# Therm_Controller.net
KiCad netlist of a schematic drawn in EasyEDA
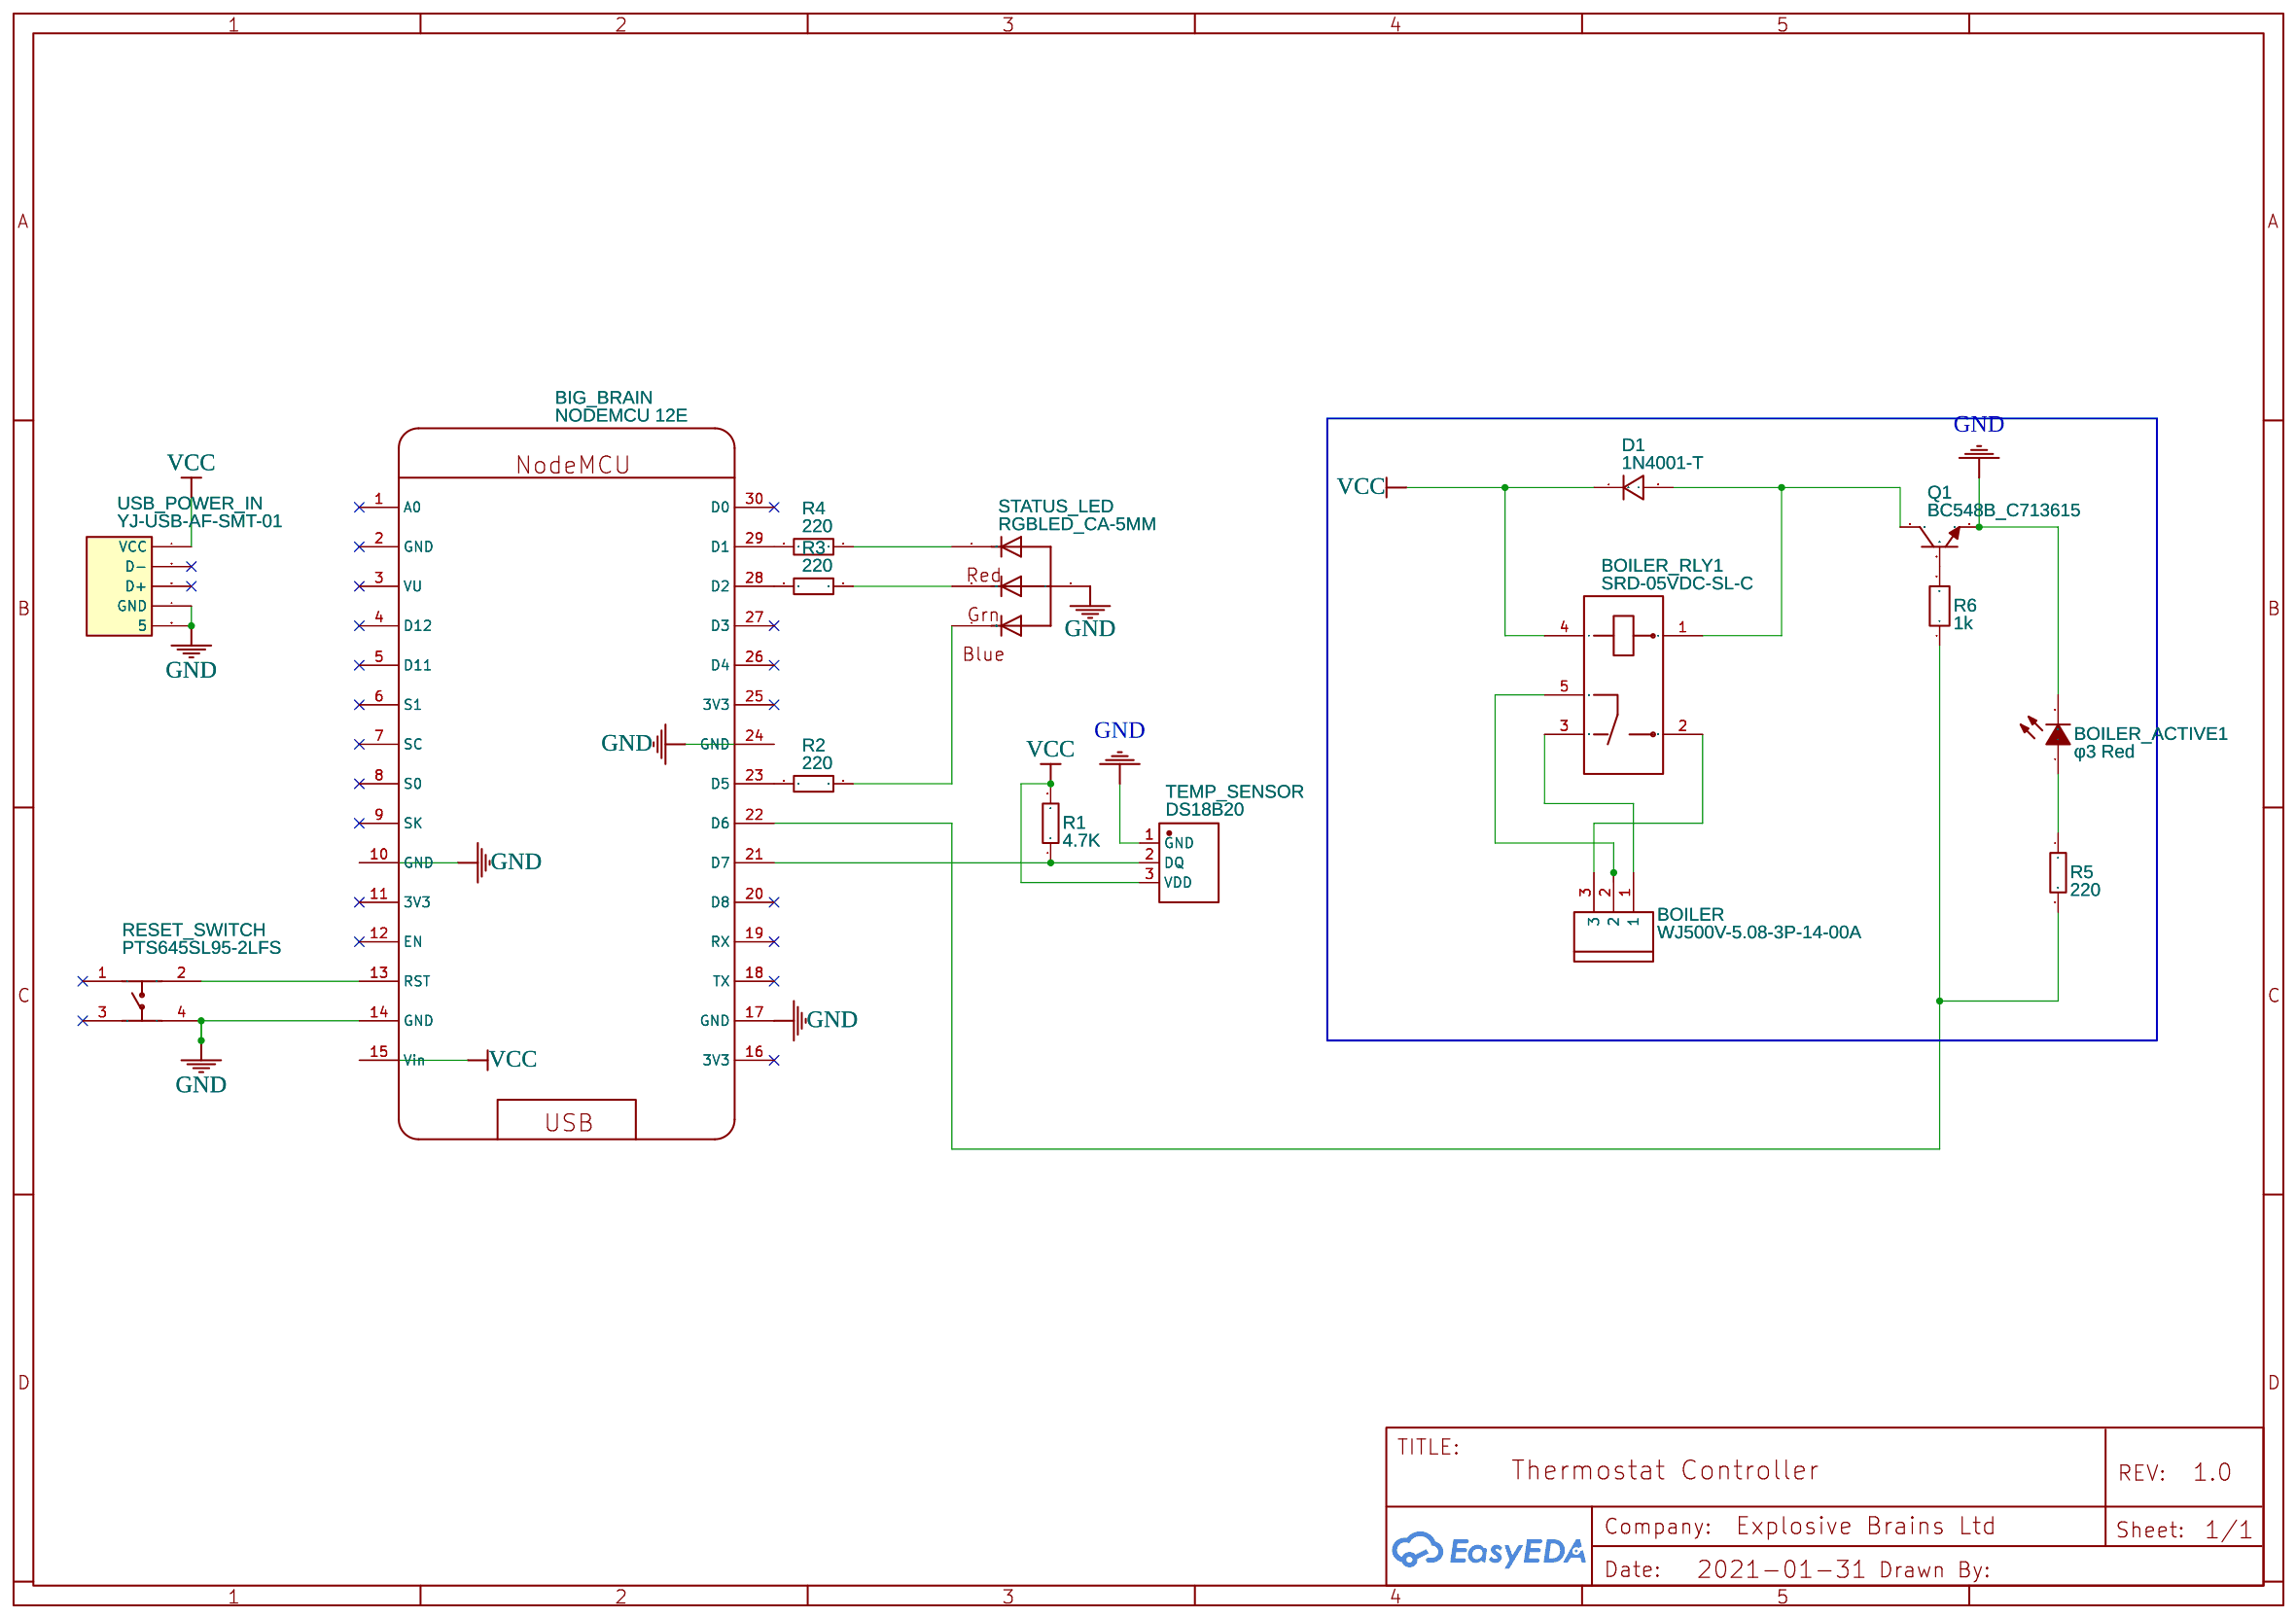
[diagram p0: schematic sheet]

(export (version "E")
  (design (tool "Eeschema 10.0.6"))
  (components
    (comp (ref "BIG_BRAIN") (value "NODEMCU 12E") (libsource (lib "") (part "NODEMCU 12E")))
    (comp (ref "BOILER")
      (value "WJ500V-5.08-3P-14-00A")
      (fields (field (name "BOM_Supplier Part") "C72334"))
      (libsource (lib "") (part "WJ500V-5.08-3P-14-00A"))
    )
    (comp (ref "BOILER_ACTIVE1")
      (value "φ3 Red")
      (fields (field (name "BOM_Supplier Part") "C39928"))
      (libsource (lib "") (part "φ3 Red"))
    )
    (comp (ref "BOILER_RLY1")
      (value "SRD-05VDC-SL-C")
      (fields (field (name "BOM_Supplier Part") "C35449"))
      (libsource (lib "") (part "SRD-05VDC-SL-C"))
    )
    (comp (ref "D1")
      (value "1N4001-T")
      (fields (field (name "BOM_Supplier Part") "C99656"))
      (libsource (lib "") (part "1N4001-T COPY"))
    )
    (comp (ref "Q1")
      (value "BC548B_C713615")
      (fields (field (name "BOM_Manufacturer Part") "BC548B") (field (name "BOM_Supplier Part") "C713615"))
      (libsource (lib "") (part "BC548B_C713615"))
    )
    (comp (ref "R1")
      (value "4.7K")
      (fields
        (field (name "BOM_Manufacturer Part") "CFR0W4J0472A50")
        (field (name "BOM_Supplier Part") "C61297")
      )
      (libsource (lib "") (part "CFR0W4J0472A50"))
    )
    (comp (ref "R2")
      (value "220")
      (fields (field (name "BOM_Supplier Part") "C120039"))
      (libsource (lib "") (part "CF1/4W-220Ω±5% T52"))
    )
    (comp (ref "R3")
      (value "220")
      (fields (field (name "BOM_Supplier Part") "C120039"))
      (libsource (lib "") (part "CF1/4W-220Ω±5% T52"))
    )
    (comp (ref "R4")
      (value "220")
      (fields (field (name "BOM_Supplier Part") "C120039"))
      (libsource (lib "") (part "CF1/4W-220Ω±5% T52"))
    )
    (comp (ref "R5")
      (value "220")
      (fields (field (name "BOM_Supplier Part") "C120039"))
      (libsource (lib "") (part "CF1/4W-220Ω±5% T52_1"))
    )
    (comp (ref "R6")
      (value "1k")
      (fields
        (field (name "BOM_Manufacturer Part") "CFR0W4J0102A50")
        (field (name "BOM_Supplier Part") "C66649")
      )
      (libsource (lib "") (part "CFR0W4J0102A50_C66649"))
    )
    (comp (ref "RESET_SWITCH")
      (value "PTS645SL95-2LFS")
      (fields (field (name "BOM_Supplier Part") "C221879"))
      (libsource (lib "") (part "PTS645SL95-2LFS"))
    )
    (comp (ref "STATUS_LED") (value "RGBLED_CA-5MM") (libsource (lib "") (part "RGBLED_CA-5MM")))
    (comp (ref "TEMP_SENSOR")
      (value "DS18B20")
      (fields (field (name "BOM_Supplier Part") "C376006"))
      (libsource (lib "") (part "DS18B20"))
    )
    (comp (ref "USB_POWER_IN")
      (value "YJ-USB-AF-SMT-01")
      (fields (field (name "BOM_Supplier Part") "C8328"))
      (libsource (lib "") (part "YJ-USB-AF-SMT-01"))
    )
  )
  (nets
    (net (code "1") (name "GND") (class "Default")
      (node (ref "BIG_BRAIN") (pin "10") (pinfunction "GND_10") (pintype "unspecified"))
      (node (ref "BIG_BRAIN") (pin "14") (pinfunction "GND_14") (pintype "unspecified"))
      (node (ref "BIG_BRAIN") (pin "17") (pinfunction "GND_17") (pintype "unspecified"))
      (node (ref "BIG_BRAIN") (pin "24") (pinfunction "GND_24") (pintype "unspecified"))
      (node (ref "BOILER_ACTIVE1") (pin "2") (pinfunction "C_2") (pintype "input"))
      (node (ref "Q1") (pin "3") (pinfunction "E_3") (pintype "input"))
      (node (ref "RESET_SWITCH") (pin "4") (pinfunction "4_4") (pintype "unspecified"))
      (node (ref "STATUS_LED") (pin "2") (pinfunction "VCC_2") (pintype "unspecified"))
      (node (ref "TEMP_SENSOR") (pin "1") (pinfunction "GND_1") (pintype "unspecified"))
      (node (ref "USB_POWER_IN") (pin "4") (pinfunction "GND_4") (pintype "input"))
      (node (ref "USB_POWER_IN") (pin "5") (pinfunction "5_5") (pintype "input"))
    )
    (net (code "2") (name "Net-(BIG_BRAIN-D1)") (class "Default")
      (node (ref "BIG_BRAIN") (pin "29") (pinfunction "D1_29") (pintype "unspecified"))
      (node (ref "R4") (pin "2") (pinfunction "2_2") (pintype "unspecified"))
    )
    (net (code "3") (name "Net-(BIG_BRAIN-D2)") (class "Default")
      (node (ref "BIG_BRAIN") (pin "28") (pinfunction "D2_28") (pintype "unspecified"))
      (node (ref "R3") (pin "2") (pinfunction "2_2") (pintype "unspecified"))
    )
    (net (code "4") (name "Net-(BIG_BRAIN-D5)") (class "Default")
      (node (ref "BIG_BRAIN") (pin "23") (pinfunction "D5_23") (pintype "unspecified"))
      (node (ref "R2") (pin "2") (pinfunction "2_2") (pintype "unspecified"))
    )
    (net (code "5") (name "Net-(BIG_BRAIN-D6)") (class "Default")
      (node (ref "BIG_BRAIN") (pin "22") (pinfunction "D6_22") (pintype "unspecified"))
      (node (ref "R5") (pin "2") (pinfunction "2_2") (pintype "unspecified"))
      (node (ref "R6") (pin "1") (pinfunction "1_1") (pintype "unspecified"))
    )
    (net (code "6") (name "Net-(BIG_BRAIN-D7)") (class "Default")
      (node (ref "BIG_BRAIN") (pin "21") (pinfunction "D7_21") (pintype "unspecified"))
      (node (ref "R1") (pin "1") (pinfunction "1_1") (pintype "input"))
      (node (ref "TEMP_SENSOR") (pin "2") (pinfunction "DQ_2") (pintype "unspecified"))
    )
    (net (code "7") (name "Net-(BIG_BRAIN-RST)") (class "Default")
      (node (ref "BIG_BRAIN") (pin "13") (pinfunction "RST_13") (pintype "unspecified"))
      (node (ref "RESET_SWITCH") (pin "2") (pinfunction "2_2") (pintype "unspecified"))
    )
    (net (code "8") (name "Net-(BOILER-Pad1)") (class "Default")
      (node (ref "BOILER") (pin "1") (pinfunction "1_1") (pintype "unspecified"))
      (node (ref "BOILER_RLY1") (pin "3") (pinfunction "3_3") (pintype "input"))
    )
    (net (code "9") (name "Net-(BOILER-Pad2)") (class "Default")
      (node (ref "BOILER") (pin "2") (pinfunction "2_2") (pintype "unspecified"))
      (node (ref "BOILER_RLY1") (pin "5") (pinfunction "5_5") (pintype "input"))
    )
    (net (code "10") (name "Net-(BOILER-Pad3)") (class "Default")
      (node (ref "BOILER") (pin "3") (pinfunction "3_3") (pintype "unspecified"))
      (node (ref "BOILER_RLY1") (pin "2") (pinfunction "2_2") (pintype "input"))
    )
    (net (code "11") (name "Net-(BOILER_ACTIVE1-A)") (class "Default")
      (node (ref "BOILER_ACTIVE1") (pin "1") (pinfunction "A_1") (pintype "input"))
      (node (ref "R5") (pin "1") (pinfunction "1_1") (pintype "unspecified"))
    )
    (net (code "12") (name "Net-(D1-A)") (class "Default")
      (node (ref "BOILER_RLY1") (pin "1") (pinfunction "1_1") (pintype "input"))
      (node (ref "D1") (pin "2") (pinfunction "A_2") (pintype "unspecified"))
      (node (ref "Q1") (pin "1") (pinfunction "C_1") (pintype "input"))
    )
    (net (code "13") (name "Net-(Q1-B)") (class "Default")
      (node (ref "Q1") (pin "2") (pinfunction "B_2") (pintype "input"))
      (node (ref "R6") (pin "2") (pinfunction "2_2") (pintype "unspecified"))
    )
    (net (code "14") (name "Net-(STATUS_LED-BLUE)") (class "Default")
      (node (ref "R2") (pin "1") (pinfunction "1_1") (pintype "unspecified"))
      (node (ref "STATUS_LED") (pin "4") (pinfunction "BLUE_4") (pintype "unspecified"))
    )
    (net (code "15") (name "Net-(STATUS_LED-GREEN)") (class "Default")
      (node (ref "R3") (pin "1") (pinfunction "1_1") (pintype "unspecified"))
      (node (ref "STATUS_LED") (pin "3") (pinfunction "GREEN_3") (pintype "unspecified"))
    )
    (net (code "16") (name "Net-(STATUS_LED-RED)") (class "Default")
      (node (ref "R4") (pin "1") (pinfunction "1_1") (pintype "unspecified"))
      (node (ref "STATUS_LED") (pin "1") (pinfunction "RED_1") (pintype "unspecified"))
    )
    (net (code "17") (name "VCC") (class "Default")
      (node (ref "BIG_BRAIN") (pin "15") (pinfunction "Vin_15") (pintype "unspecified"))
      (node (ref "BOILER_RLY1") (pin "4") (pinfunction "4_4") (pintype "input"))
      (node (ref "D1") (pin "1") (pinfunction "C_1") (pintype "unspecified"))
      (node (ref "R1") (pin "2") (pinfunction "2_2") (pintype "input"))
      (node (ref "TEMP_SENSOR") (pin "3") (pinfunction "VDD_3") (pintype "unspecified"))
      (node (ref "USB_POWER_IN") (pin "1") (pinfunction "VCC_1") (pintype "input"))
    )
    (net (code "18") (name "unconnected-(BIG_BRAIN-3V3-Pad11)") (class "Default")
      (node (ref "BIG_BRAIN") (pin "11") (pinfunction "3V3_11") (pintype "unspecified+no_connect"))
    )
    (net (code "19") (name "unconnected-(BIG_BRAIN-3V3-Pad16)") (class "Default")
      (node (ref "BIG_BRAIN") (pin "16") (pinfunction "3V3_16") (pintype "unspecified+no_connect"))
    )
    (net (code "20") (name "unconnected-(BIG_BRAIN-3V3-Pad25)") (class "Default")
      (node (ref "BIG_BRAIN") (pin "25") (pinfunction "3V3_25") (pintype "unspecified+no_connect"))
    )
    (net (code "21") (name "unconnected-(BIG_BRAIN-A0-Pad1)") (class "Default")
      (node (ref "BIG_BRAIN") (pin "1") (pinfunction "A0_1") (pintype "unspecified+no_connect"))
    )
    (net (code "22") (name "unconnected-(BIG_BRAIN-D0-Pad30)") (class "Default")
      (node (ref "BIG_BRAIN") (pin "30") (pinfunction "D0_30") (pintype "unspecified+no_connect"))
    )
    (net (code "23") (name "unconnected-(BIG_BRAIN-D3-Pad27)") (class "Default")
      (node (ref "BIG_BRAIN") (pin "27") (pinfunction "D3_27") (pintype "unspecified+no_connect"))
    )
    (net (code "24") (name "unconnected-(BIG_BRAIN-D4-Pad26)") (class "Default")
      (node (ref "BIG_BRAIN") (pin "26") (pinfunction "D4_26") (pintype "unspecified+no_connect"))
    )
    (net (code "25") (name "unconnected-(BIG_BRAIN-D8-Pad20)") (class "Default")
      (node (ref "BIG_BRAIN") (pin "20") (pinfunction "D8_20") (pintype "unspecified+no_connect"))
    )
    (net (code "26") (name "unconnected-(BIG_BRAIN-D11-Pad5)") (class "Default")
      (node (ref "BIG_BRAIN") (pin "5") (pinfunction "D11_5") (pintype "unspecified+no_connect"))
    )
    (net (code "27") (name "unconnected-(BIG_BRAIN-D12-Pad4)") (class "Default")
      (node (ref "BIG_BRAIN") (pin "4") (pinfunction "D12_4") (pintype "unspecified+no_connect"))
    )
    (net (code "28") (name "unconnected-(BIG_BRAIN-EN-Pad12)") (class "Default")
      (node (ref "BIG_BRAIN") (pin "12") (pinfunction "EN_12") (pintype "unspecified+no_connect"))
    )
    (net (code "29") (name "unconnected-(BIG_BRAIN-GND-Pad2)") (class "Default")
      (node (ref "BIG_BRAIN") (pin "2") (pinfunction "GND_2") (pintype "unspecified+no_connect"))
    )
    (net (code "30") (name "unconnected-(BIG_BRAIN-RX-Pad19)") (class "Default")
      (node (ref "BIG_BRAIN") (pin "19") (pinfunction "RX_19") (pintype "unspecified+no_connect"))
    )
    (net (code "31") (name "unconnected-(BIG_BRAIN-S0-Pad8)") (class "Default")
      (node (ref "BIG_BRAIN") (pin "8") (pinfunction "S0_8") (pintype "unspecified+no_connect"))
    )
    (net (code "32") (name "unconnected-(BIG_BRAIN-S1-Pad6)") (class "Default")
      (node (ref "BIG_BRAIN") (pin "6") (pinfunction "S1_6") (pintype "unspecified+no_connect"))
    )
    (net (code "33") (name "unconnected-(BIG_BRAIN-SC-Pad7)") (class "Default")
      (node (ref "BIG_BRAIN") (pin "7") (pinfunction "SC_7") (pintype "unspecified+no_connect"))
    )
    (net (code "34") (name "unconnected-(BIG_BRAIN-SK-Pad9)") (class "Default")
      (node (ref "BIG_BRAIN") (pin "9") (pinfunction "SK_9") (pintype "unspecified+no_connect"))
    )
    (net (code "35") (name "unconnected-(BIG_BRAIN-TX-Pad18)") (class "Default")
      (node (ref "BIG_BRAIN") (pin "18") (pinfunction "TX_18") (pintype "unspecified+no_connect"))
    )
    (net (code "36") (name "unconnected-(BIG_BRAIN-VU-Pad3)") (class "Default")
      (node (ref "BIG_BRAIN") (pin "3") (pinfunction "VU_3") (pintype "unspecified+no_connect"))
    )
    (net (code "37") (name "unconnected-(RESET_SWITCH-Pad1)") (class "Default")
      (node (ref "RESET_SWITCH") (pin "1") (pinfunction "1_1") (pintype "unspecified+no_connect"))
    )
    (net (code "38") (name "unconnected-(RESET_SWITCH-Pad3)") (class "Default")
      (node (ref "RESET_SWITCH") (pin "3") (pinfunction "3_3") (pintype "unspecified+no_connect"))
    )
    (net (code "39") (name "unconnected-(USB_POWER_IN-D+-Pad3)") (class "Default")
      (node (ref "USB_POWER_IN") (pin "3") (pinfunction "D+_3") (pintype "input+no_connect"))
    )
    (net (code "40") (name "unconnected-(USB_POWER_IN-D--Pad2)") (class "Default")
      (node (ref "USB_POWER_IN") (pin "2") (pinfunction "D-_2") (pintype "input+no_connect"))
    )
  )
)
